# OnOnfre_dual_parafuso_estores_beta.net
KiCad netlist of a schematic drawn in EAGLE
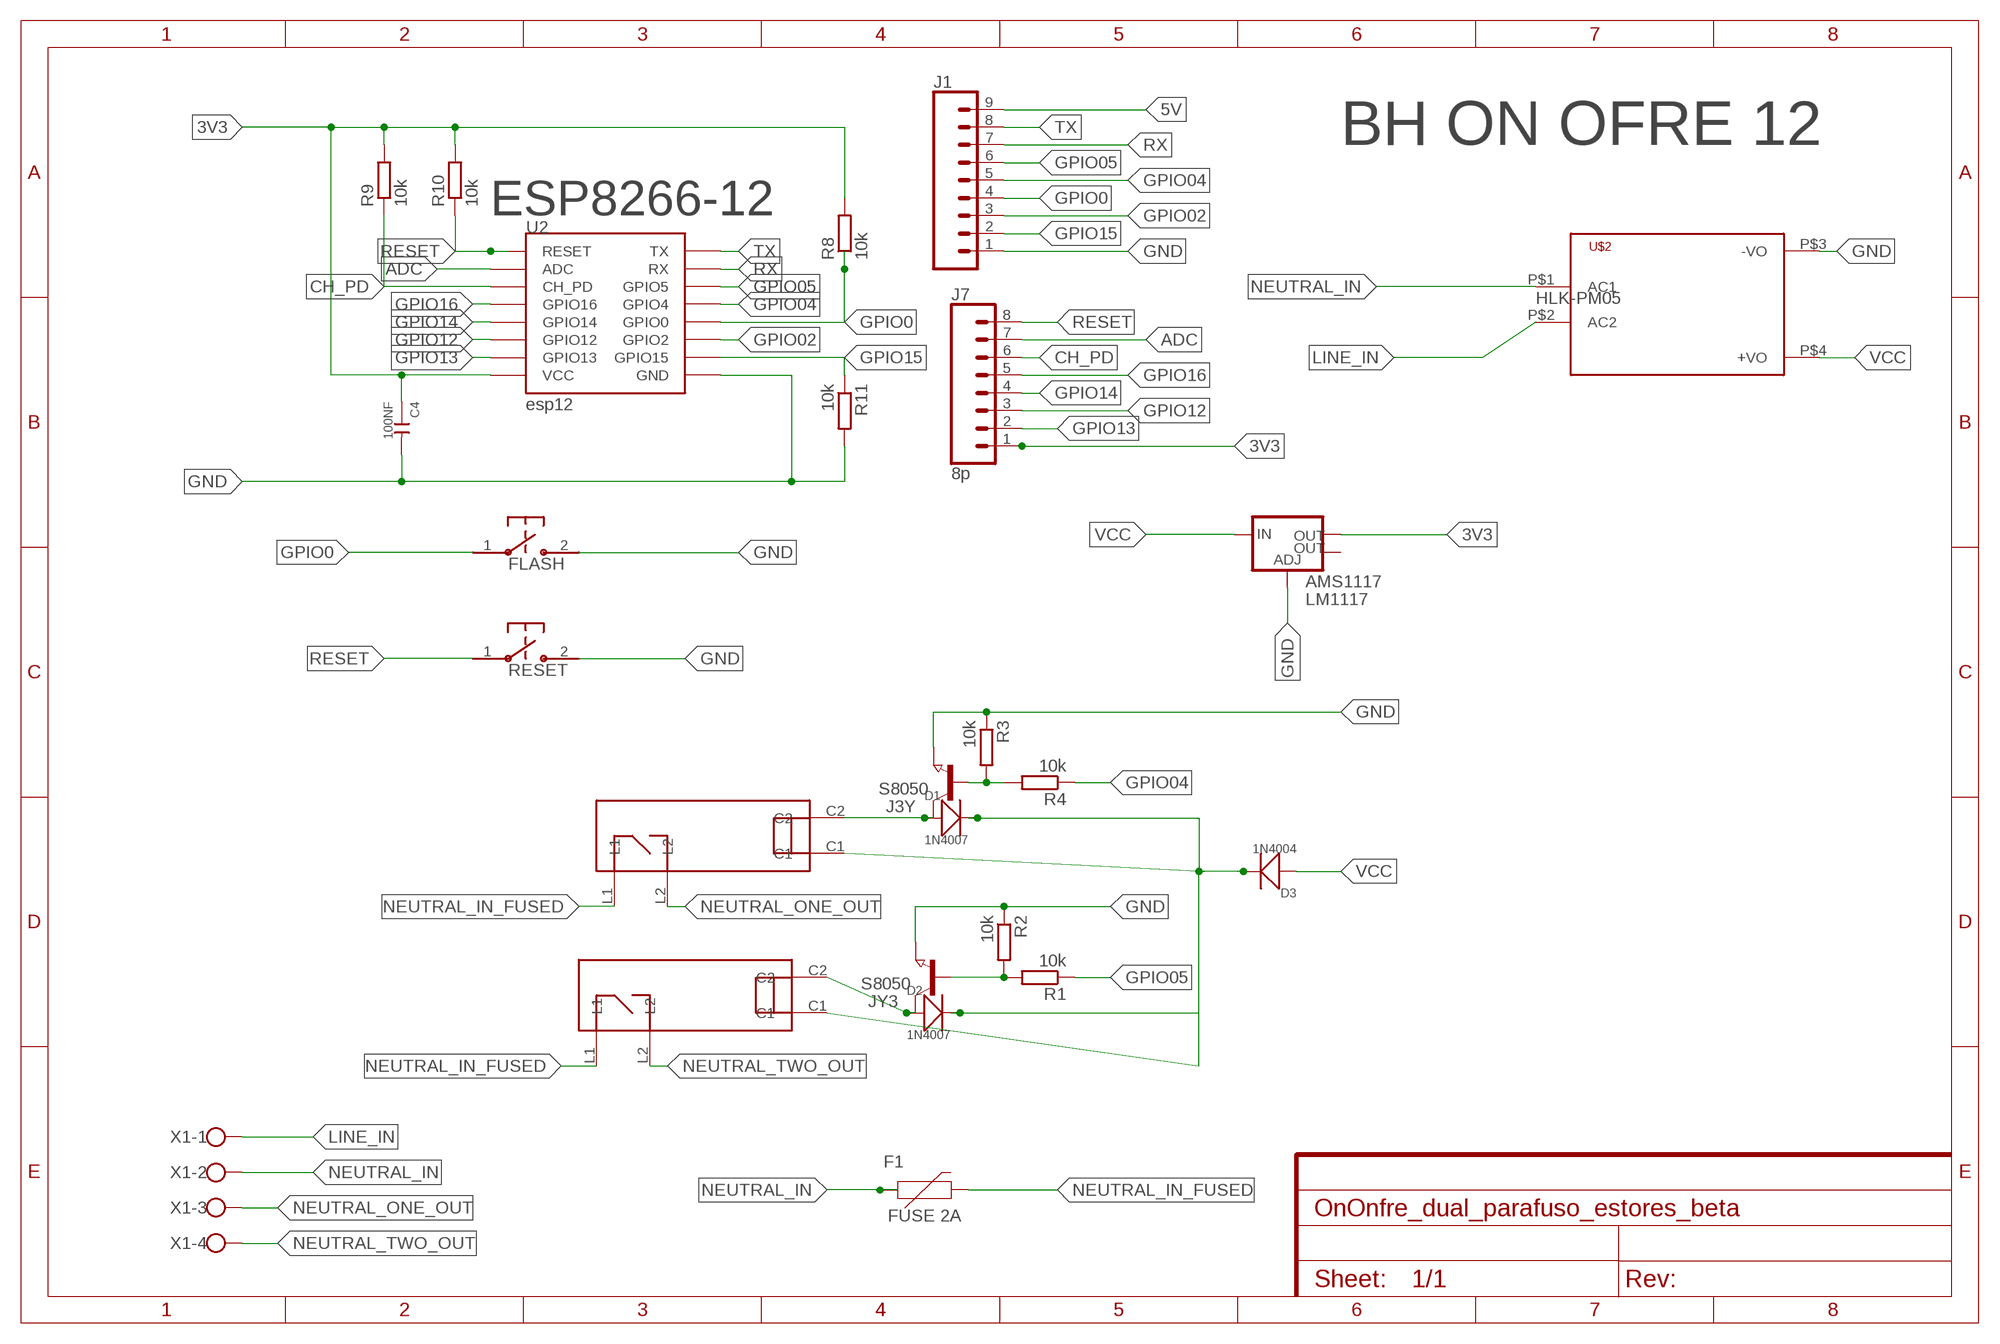
[diagram p0: schematic, sheet 1]

(export (version "E")
  (design (tool "Eeschema 10.0.6"))
  (components
    (comp (ref "AMS1117")
      (value "LM1117")
      (footprint "eagle-import:SOT223")
      (libsource (lib "eagle-import") (part "V_REG_LM1117SOT223"))
    )
    (comp (ref "C4")
      (value "100NF")
      (footprint "eagle-import:C1206")
      (fields (field (name "MPN") "CC1206KKX7RCBB102"))
      (libsource (lib "eagle-import") (part "CERAMIC-1NF-1KV-10%-X7R?(1206)"))
    )
    (comp (ref "D1")
      (value "1N4007")
      (footprint "eagle-import:DO-214AC")
      (libsource (lib "eagle-import") (part "DIODE-GEN-PURPOSE-1KV-1A(DO-214AC)"))
    )
    (comp (ref "D2")
      (value "1N4007")
      (footprint "eagle-import:DO-214AC")
      (libsource (lib "eagle-import") (part "DIODE-GEN-PURPOSE-1KV-1A(DO-214AC)"))
    )
    (comp (ref "D3")
      (value "1N4004")
      (footprint "eagle-import:DO-214AC")
      (fields (field (name "MPN") "1N4007"))
      (libsource (lib "eagle-import") (part "DIODE-GEN-PURPOSE-1KV-1A(DO-214AC)"))
    )
    (comp (ref "F1")
      (value "FUSE 2A")
      (footprint "eagle-import:PTH")
      (libsource (lib "eagle-import") (part "PPTC_PTH"))
    )
    (comp (ref "FLASH")
      (value "B3U-1000P-2P-SMD")
      (footprint "eagle-import:B3U-1000P")
      (fields (field (name "MANUFACTURER") "Omron") (field (name "MPN") "B3U-1000P"))
      (libsource (lib "eagle-import") (part "B3U-1000P"))
    )
    (comp (ref "J1")
      (value "CONN_09")
      (footprint "eagle-import:1X09")
      (libsource (lib "eagle-import") (part "CONN_09"))
    )
    (comp (ref "J3Y")
      (value "S8050")
      (footprint "eagle-import:SOT23")
      (libsource (lib "eagle-import") (part "NPN-TRANSISTOR_SOT23"))
    )
    (comp (ref "J7")
      (value "8p")
      (footprint "eagle-import:1X08")
      (libsource (lib "eagle-import") (part "CONN_08{dblquote}"))
    )
    (comp (ref "JY3")
      (value "S8050")
      (footprint "eagle-import:SOT23")
      (libsource (lib "eagle-import") (part "NPN-TRANSISTOR_SOT23"))
    )
    (comp (ref "R1")
      (value "10k")
      (footprint "eagle-import:R0603")
      (libsource (lib "eagle-import") (part "R-EU_R0603"))
    )
    (comp (ref "R2")
      (value "10k")
      (footprint "eagle-import:R0603")
      (libsource (lib "eagle-import") (part "R-EU_R0603"))
    )
    (comp (ref "R3")
      (value "10k")
      (footprint "eagle-import:R0603")
      (libsource (lib "eagle-import") (part "R-EU_R0603"))
    )
    (comp (ref "R4")
      (value "10k")
      (footprint "eagle-import:R0603")
      (libsource (lib "eagle-import") (part "R-EU_R0603"))
    )
    (comp (ref "R8")
      (value "10k")
      (footprint "eagle-import:R0603")
      (libsource (lib "eagle-import") (part "R-EU_R0603"))
    )
    (comp (ref "R9")
      (value "10k")
      (footprint "eagle-import:R0603")
      (libsource (lib "eagle-import") (part "R-EU_R0603"))
    )
    (comp (ref "R10")
      (value "10k")
      (footprint "eagle-import:R0603")
      (libsource (lib "eagle-import") (part "R-EU_R0603"))
    )
    (comp (ref "R11")
      (value "10k")
      (footprint "eagle-import:R0603")
      (libsource (lib "eagle-import") (part "R-EU_R0603"))
    )
    (comp (ref "RESET")
      (value "B3U-1000P-2P-SMD")
      (footprint "eagle-import:B3U-1000P")
      (fields (field (name "MANUFACTURER") "Omron") (field (name "MPN") "B3U-1000P"))
      (libsource (lib "eagle-import") (part "B3U-1000P"))
    )
    (comp (ref "U$1")
      (value "HF46F")
      (footprint "eagle-import:HF46F")
      (libsource (lib "eagle-import") (part "HF46F"))
    )
    (comp (ref "U$2")
      (value "HKLPM01")
      (footprint "eagle-import:HKLPM01")
      (libsource (lib "eagle-import") (part "HKLPM01"))
    )
    (comp (ref "U$3")
      (value "HF46F")
      (footprint "eagle-import:HF46F")
      (libsource (lib "eagle-import") (part "HF46F"))
    )
    (comp (ref "U2")
      (value "esp12")
      (footprint "eagle-import:ESP12-SMD")
      (libsource (lib "eagle-import") (part "ESP12SMD"))
    )
    (comp (ref "X1")
      (value "W237-4")
      (footprint "eagle-import:W237-4")
      (libsource (lib "eagle-import") (part "W237-4"))
    )
  )
  (nets
    (net (code "1") (name "3V3") (class "Default")
      (node (ref "AMS1117") (pin "2") (pinfunction "OUT_2") (pintype "output"))
      (node (ref "C4") (pin "1") (pinfunction "1_1") (pintype "passive"))
      (node (ref "J7") (pin "1") (pinfunction "1_1") (pintype "passive"))
      (node (ref "R10") (pin "2") (pinfunction "2_2") (pintype "passive"))
      (node (ref "R8") (pin "2") (pinfunction "2_2") (pintype "passive"))
      (node (ref "R9") (pin "2") (pinfunction "2_2") (pintype "passive"))
      (node (ref "U2") (pin "VCC") (pinfunction "VCC_VCC") (pintype "bidirectional"))
    )
    (net (code "2") (name "5V") (class "Default")
      (node (ref "D1") (pin "2") (pinfunction "-_2") (pintype "passive"))
      (node (ref "D2") (pin "2") (pinfunction "-_2") (pintype "passive"))
      (node (ref "D3") (pin "2") (pinfunction "-_2") (pintype "passive"))
      (node (ref "J1") (pin "9") (pinfunction "9_9") (pintype "passive"))
      (node (ref "U$1") (pin "C1") (pinfunction "C1_C1") (pintype "bidirectional"))
      (node (ref "U$3") (pin "C1") (pinfunction "C1_C1") (pintype "bidirectional"))
    )
    (net (code "3") (name "ADC") (class "Default")
      (node (ref "J7") (pin "7") (pinfunction "7_7") (pintype "passive"))
      (node (ref "U2") (pin "ADC") (pinfunction "ADC_ADC") (pintype "bidirectional"))
    )
    (net (code "4") (name "CH_PD") (class "Default")
      (node (ref "J7") (pin "6") (pinfunction "6_6") (pintype "passive"))
      (node (ref "R9") (pin "1") (pinfunction "1_1") (pintype "passive"))
      (node (ref "U2") (pin "CH_PD") (pinfunction "CH_PD_CH_PD") (pintype "bidirectional"))
    )
    (net (code "5") (name "GND") (class "Default")
      (node (ref "AMS1117") (pin "1") (pinfunction "ADJ_1") (pintype "input"))
      (node (ref "C4") (pin "2") (pinfunction "2_2") (pintype "passive"))
      (node (ref "FLASH") (pin "2") (pinfunction "P$2_2") (pintype "passive"))
      (node (ref "J1") (pin "1") (pinfunction "1_1") (pintype "passive"))
      (node (ref "J3Y") (pin "2") (pinfunction "E_2") (pintype "passive"))
      (node (ref "JY3") (pin "2") (pinfunction "E_2") (pintype "passive"))
      (node (ref "R11") (pin "2") (pinfunction "2_2") (pintype "passive"))
      (node (ref "R2") (pin "1") (pinfunction "1_1") (pintype "passive"))
      (node (ref "R3") (pin "1") (pinfunction "1_1") (pintype "passive"))
      (node (ref "RESET") (pin "2") (pinfunction "P$2_2") (pintype "passive"))
      (node (ref "U$2") (pin "P$3") (pinfunction "-VO_P$3") (pintype "bidirectional"))
      (node (ref "U2") (pin "GND") (pinfunction "GND_GND") (pintype "bidirectional"))
    )
    (net (code "6") (name "GPIO0") (class "Default")
      (node (ref "FLASH") (pin "1") (pinfunction "P$1_1") (pintype "passive"))
      (node (ref "J1") (pin "4") (pinfunction "4_4") (pintype "passive"))
      (node (ref "R8") (pin "1") (pinfunction "1_1") (pintype "passive"))
      (node (ref "U2") (pin "GPIO0") (pinfunction "GPIO0_GPIO0") (pintype "bidirectional"))
    )
    (net (code "7") (name "GPIO02") (class "Default")
      (node (ref "J1") (pin "3") (pinfunction "3_3") (pintype "passive"))
      (node (ref "U2") (pin "GPIO2") (pinfunction "GPIO2_GPIO2") (pintype "bidirectional"))
    )
    (net (code "8") (name "GPIO04") (class "Default")
      (node (ref "J1") (pin "5") (pinfunction "5_5") (pintype "passive"))
      (node (ref "R4") (pin "1") (pinfunction "1_1") (pintype "passive"))
      (node (ref "U2") (pin "GPIO4") (pinfunction "GPIO4_GPIO4") (pintype "bidirectional"))
    )
    (net (code "9") (name "GPIO05") (class "Default")
      (node (ref "J1") (pin "6") (pinfunction "6_6") (pintype "passive"))
      (node (ref "R1") (pin "1") (pinfunction "1_1") (pintype "passive"))
      (node (ref "U2") (pin "GPIO5") (pinfunction "GPIO5_GPIO5") (pintype "bidirectional"))
    )
    (net (code "10") (name "GPIO12") (class "Default")
      (node (ref "J7") (pin "3") (pinfunction "3_3") (pintype "passive"))
      (node (ref "U2") (pin "GPIO12") (pinfunction "GPIO12_GPIO12") (pintype "bidirectional"))
    )
    (net (code "11") (name "GPIO13") (class "Default")
      (node (ref "J7") (pin "2") (pinfunction "2_2") (pintype "passive"))
      (node (ref "U2") (pin "GPIO13") (pinfunction "GPIO13_GPIO13") (pintype "bidirectional"))
    )
    (net (code "12") (name "GPIO14") (class "Default")
      (node (ref "J7") (pin "4") (pinfunction "4_4") (pintype "passive"))
      (node (ref "U2") (pin "GPIO14") (pinfunction "GPIO14_GPIO14") (pintype "bidirectional"))
    )
    (net (code "13") (name "GPIO15") (class "Default")
      (node (ref "J1") (pin "2") (pinfunction "2_2") (pintype "passive"))
      (node (ref "R11") (pin "1") (pinfunction "1_1") (pintype "passive"))
      (node (ref "U2") (pin "GPIO15") (pinfunction "GPIO15_GPIO15") (pintype "bidirectional"))
    )
    (net (code "14") (name "GPIO16") (class "Default")
      (node (ref "J7") (pin "5") (pinfunction "5_5") (pintype "passive"))
      (node (ref "U2") (pin "GPIO16") (pinfunction "GPIO16_GPIO16") (pintype "bidirectional"))
    )
    (net (code "15") (name "LINE_IN") (class "Default")
      (node (ref "U$2") (pin "P$2") (pinfunction "AC2_P$2") (pintype "bidirectional"))
      (node (ref "X1") (pin "1") (pinfunction "KL_1") (pintype "passive"))
    )
    (net (code "16") (name "NEUTRAL_IN") (class "Default")
      (node (ref "F1") (pin "P$1") (pinfunction "1_P$1") (pintype "bidirectional"))
      (node (ref "U$2") (pin "P$1") (pinfunction "AC1_P$1") (pintype "bidirectional"))
      (node (ref "X1") (pin "2") (pinfunction "KL_2") (pintype "passive"))
    )
    (net (code "17") (name "NEUTRAL_IN_FUSED") (class "Default")
      (node (ref "F1") (pin "P$2") (pinfunction "2_P$2") (pintype "bidirectional"))
      (node (ref "U$1") (pin "L1") (pinfunction "L1_L1") (pintype "bidirectional"))
      (node (ref "U$3") (pin "L1") (pinfunction "L1_L1") (pintype "bidirectional"))
    )
    (net (code "18") (name "NEUTRAL_ONE_OUT") (class "Default")
      (node (ref "U$1") (pin "L2") (pinfunction "L2_L2") (pintype "bidirectional"))
      (node (ref "X1") (pin "3") (pinfunction "KL_3") (pintype "passive"))
    )
    (net (code "19") (name "NEUTRAL_TWO_OUT") (class "Default")
      (node (ref "U$3") (pin "L2") (pinfunction "L2_L2") (pintype "bidirectional"))
      (node (ref "X1") (pin "4") (pinfunction "KL_4") (pintype "passive"))
    )
    (net (code "20") (name "Net-(D1-+)") (class "Default")
      (node (ref "D1") (pin "1") (pinfunction "+_1") (pintype "passive"))
      (node (ref "J3Y") (pin "3") (pinfunction "C_3") (pintype "passive"))
      (node (ref "U$1") (pin "C2") (pinfunction "C2_C2") (pintype "bidirectional"))
    )
    (net (code "21") (name "Net-(D2-+)") (class "Default")
      (node (ref "D2") (pin "1") (pinfunction "+_1") (pintype "passive"))
      (node (ref "JY3") (pin "3") (pinfunction "C_3") (pintype "passive"))
      (node (ref "U$3") (pin "C2") (pinfunction "C2_C2") (pintype "bidirectional"))
    )
    (net (code "22") (name "Net-(J3Y-B)") (class "Default")
      (node (ref "J3Y") (pin "1") (pinfunction "B_1") (pintype "passive"))
      (node (ref "R3") (pin "2") (pinfunction "2_2") (pintype "passive"))
      (node (ref "R4") (pin "2") (pinfunction "2_2") (pintype "passive"))
    )
    (net (code "23") (name "Net-(JY3-B)") (class "Default")
      (node (ref "JY3") (pin "1") (pinfunction "B_1") (pintype "passive"))
      (node (ref "R1") (pin "2") (pinfunction "2_2") (pintype "passive"))
      (node (ref "R2") (pin "2") (pinfunction "2_2") (pintype "passive"))
    )
    (net (code "24") (name "RESET") (class "Default")
      (node (ref "J7") (pin "8") (pinfunction "8_8") (pintype "passive"))
      (node (ref "R10") (pin "1") (pinfunction "1_1") (pintype "passive"))
      (node (ref "RESET") (pin "1") (pinfunction "P$1_1") (pintype "passive"))
      (node (ref "U2") (pin "RESET") (pinfunction "RESET_RESET") (pintype "bidirectional"))
    )
    (net (code "25") (name "RX") (class "Default")
      (node (ref "J1") (pin "7") (pinfunction "7_7") (pintype "passive"))
      (node (ref "U2") (pin "RXD0") (pinfunction "RX_RXD0") (pintype "bidirectional"))
    )
    (net (code "26") (name "TX") (class "Default")
      (node (ref "J1") (pin "8") (pinfunction "8_8") (pintype "passive"))
      (node (ref "U2") (pin "TXD0") (pinfunction "TX_TXD0") (pintype "bidirectional"))
    )
    (net (code "27") (name "VCC") (class "Default")
      (node (ref "AMS1117") (pin "3") (pinfunction "IN_3") (pintype "input"))
      (node (ref "D3") (pin "1") (pinfunction "+_1") (pintype "passive"))
      (node (ref "U$2") (pin "P$4") (pinfunction "+VO_P$4") (pintype "bidirectional"))
    )
    (net (code "28") (name "unconnected-(AMS1117-OUT-Pad4)") (class "Default")
      (node (ref "AMS1117") (pin "4") (pinfunction "OUT_4") (pintype "output"))
    )
  )
)
